# ToF_Sensor.net
KiCad netlist of a schematic drawn in Altium Designer
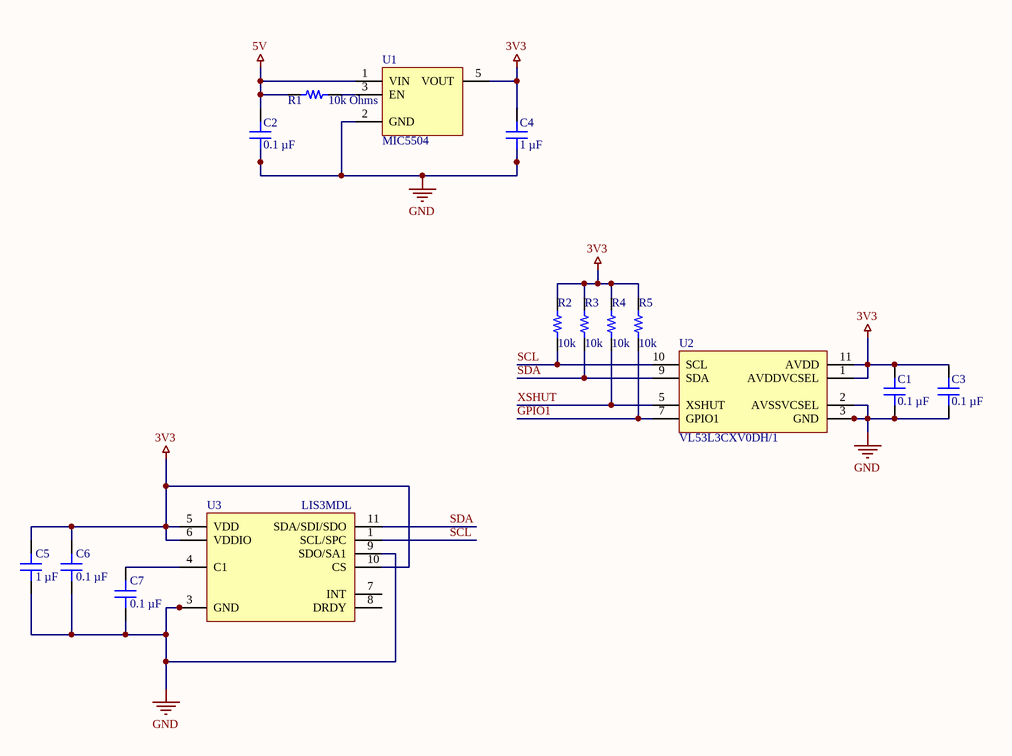
[diagram p0: ToF_Sensor.SchDoc]

(export (version "E")
  (design (tool "Eeschema 10.0.6"))
  (components
    (comp (ref "C1")
      (value "0.1 µF")
      (footprint "CAP 0402_1005")
      (description "CAP CER 0.1UF 16V X7R 0402")
      (fields (field (name "PART NUMBER") "C0402C104K4RACAUTO") (field (name "MANUFACTURER") "KEMET"))
      (libsource (lib "Celestial Altium Library - altium_library") (part "Capacitor"))
    )
    (comp (ref "C2")
      (value "0.1 µF")
      (footprint "CAP 0402_1005")
      (description "CAP CER 0.1UF 16V X7R 0402")
      (fields (field (name "PART NUMBER") "C0402C104K4RACAUTO") (field (name "MANUFACTURER") "KEMET"))
      (libsource (lib "Celestial Altium Library - altium_library") (part "Capacitor"))
    )
    (comp (ref "C3")
      (value "0.1 µF")
      (footprint "CAP 0402_1005")
      (description "CAP CER 0.1UF 16V X7R 0402")
      (fields (field (name "PART NUMBER") "C0402C104K4RACAUTO") (field (name "MANUFACTURER") "KEMET"))
      (libsource (lib "Celestial Altium Library - altium_library") (part "Capacitor"))
    )
    (comp (ref "C4")
      (value "1 µF")
      (footprint "CAP 0402_1005")
      (description "CAP CER 0.1UF 16V X7R 0402")
      (fields (field (name "PART NUMBER") "C0402C104K4RACAUTO") (field (name "MANUFACTURER") "KEMET"))
      (libsource (lib "Celestial Altium Library - altium_library") (part "Capacitor"))
    )
    (comp (ref "C5")
      (value "1 µF")
      (footprint "CAP 0402_1005")
      (description "CAP CER 0.1UF 16V X7R 0402")
      (fields (field (name "PART NUMBER") "C0402C104K4RACAUTO") (field (name "MANUFACTURER") "KEMET"))
      (libsource (lib "Celestial Altium Library - altium_library") (part "Capacitor"))
    )
    (comp (ref "C6")
      (value "0.1 µF")
      (footprint "CAP 0402_1005")
      (description "CAP CER 0.1UF 16V X7R 0402")
      (fields (field (name "PART NUMBER") "C0402C104K4RACAUTO") (field (name "MANUFACTURER") "KEMET"))
      (libsource (lib "Celestial Altium Library - altium_library") (part "Capacitor"))
    )
    (comp (ref "C7")
      (value "0.1 µF")
      (footprint "CAP 0402_1005")
      (description "CAP CER 0.1UF 16V X7R 0402")
      (fields (field (name "PART NUMBER") "C0402C104K4RACAUTO") (field (name "MANUFACTURER") "KEMET"))
      (libsource (lib "Celestial Altium Library - altium_library") (part "Capacitor"))
    )
    (comp (ref "R1")
      (value "10k Ohms")
      (footprint "RES 0402_1005")
      (description "RES 330 OHM 5% 1/16W 0402")
      (fields (field (name "PART NUMBER") "CRCW0402330RJNEDC") (field (name "MANUFACTURER") "Vishay Dale"))
      (libsource (lib "Celestial Altium Library - altium_library") (part "Resistor"))
    )
    (comp (ref "R2")
      (value "10k")
      (footprint "RES 0402_1005")
      (description "RES 330 OHM 5% 1/16W 0402")
      (fields (field (name "PART NUMBER") "CRCW0402330RJNEDC") (field (name "MANUFACTURER") "Vishay Dale"))
      (libsource (lib "Celestial Altium Library - altium_library") (part "Resistor"))
    )
    (comp (ref "R3")
      (value "10k")
      (footprint "RES 0402_1005")
      (description "RES 330 OHM 5% 1/16W 0402")
      (fields (field (name "PART NUMBER") "CRCW0402330RJNEDC") (field (name "MANUFACTURER") "Vishay Dale"))
      (libsource (lib "Celestial Altium Library - altium_library") (part "Resistor"))
    )
    (comp (ref "R4")
      (value "10k")
      (footprint "RES 0402_1005")
      (description "RES 330 OHM 5% 1/16W 0402")
      (fields (field (name "PART NUMBER") "CRCW0402330RJNEDC") (field (name "MANUFACTURER") "Vishay Dale"))
      (libsource (lib "Celestial Altium Library - altium_library") (part "Resistor"))
    )
    (comp (ref "R5")
      (value "10k")
      (footprint "RES 0402_1005")
      (description "RES 330 OHM 5% 1/16W 0402")
      (fields (field (name "PART NUMBER") "CRCW0402330RJNEDC") (field (name "MANUFACTURER") "Vishay Dale"))
      (libsource (lib "Celestial Altium Library - altium_library") (part "Resistor"))
    )
    (comp (ref "U1")
      (value "MIC5504")
      (footprint "TI SOT-23-5 DBV")
      (description "3.3V LDO")
      (libsource (lib "IC") (part "MIC5504-3.3YM5"))
    )
    (comp (ref "U2")
      (value "VL53L3CXV0DH/1")
      (footprint "XDCR_VL53L3CXV0DH/1")
      (description "Optical Sensor 118.110 (3m) I2C Output")
      (fields (field (name "MF") "STMicroelectronics"))
      (libsource (lib "IC") (part "VL53L3CXV0DH/1"))
    )
    (comp (ref "U3")
      (value "LIS3MDL")
      (footprint "LGA12_ST")
      (description "Magnetometer")
      (libsource (lib "IC") (part "LIS3MDL"))
    )
  )
  (nets
    (net (code "1") (name "/GPIO1") (class "Default")
      (node (ref "R5") (pin "2") (pinfunction "2_2") (pintype "passive"))
      (node (ref "U2") (pin "7") (pinfunction "GPIO1_7") (pintype "passive"))
    )
    (net (code "2") (name "/SCL") (class "Default")
      (node (ref "R2") (pin "2") (pinfunction "2_2") (pintype "passive"))
      (node (ref "U2") (pin "10") (pinfunction "SCL_10") (pintype "passive"))
      (node (ref "U3") (pin "1") (pinfunction "SCL/SPC_1") (pintype "passive"))
    )
    (net (code "3") (name "/SDA") (class "Default")
      (node (ref "R3") (pin "2") (pinfunction "2_2") (pintype "passive"))
      (node (ref "U2") (pin "9") (pinfunction "SDA_9") (pintype "passive"))
      (node (ref "U3") (pin "11") (pinfunction "SDA/SDI/SDO_11") (pintype "passive"))
    )
    (net (code "4") (name "/XSHUT") (class "Default")
      (node (ref "R4") (pin "2") (pinfunction "2_2") (pintype "passive"))
      (node (ref "U2") (pin "5") (pinfunction "XSHUT_5") (pintype "passive"))
    )
    (net (code "5") (name "3V3") (class "Default")
      (node (ref "C1") (pin "2") (pinfunction "2_2") (pintype "passive"))
      (node (ref "C3") (pin "2") (pinfunction "2_2") (pintype "passive"))
      (node (ref "C4") (pin "2") (pinfunction "2_2") (pintype "passive"))
      (node (ref "C5") (pin "1") (pinfunction "1_1") (pintype "passive"))
      (node (ref "C6") (pin "1") (pinfunction "1_1") (pintype "passive"))
      (node (ref "R2") (pin "1") (pinfunction "1_1") (pintype "passive"))
      (node (ref "R3") (pin "1") (pinfunction "1_1") (pintype "passive"))
      (node (ref "R4") (pin "1") (pinfunction "1_1") (pintype "passive"))
      (node (ref "R5") (pin "1") (pinfunction "1_1") (pintype "passive"))
      (node (ref "U1") (pin "5") (pinfunction "VOUT_5") (pintype "passive"))
      (node (ref "U2") (pin "1") (pinfunction "AVDDVCSEL_1") (pintype "passive"))
      (node (ref "U2") (pin "11") (pinfunction "AVDD_11") (pintype "passive"))
      (node (ref "U3") (pin "10") (pinfunction "CS_10") (pintype "passive"))
      (node (ref "U3") (pin "5") (pinfunction "VDD_5") (pintype "passive"))
      (node (ref "U3") (pin "6") (pinfunction "VDDIO_6") (pintype "passive"))
    )
    (net (code "6") (name "5V") (class "Default")
      (node (ref "C2") (pin "2") (pinfunction "2_2") (pintype "passive"))
      (node (ref "R1") (pin "2") (pinfunction "2_2") (pintype "passive"))
      (node (ref "U1") (pin "1") (pinfunction "VIN_1") (pintype "passive"))
    )
    (net (code "7") (name "GND") (class "Default")
      (node (ref "C1") (pin "1") (pinfunction "1_1") (pintype "passive"))
      (node (ref "C2") (pin "1") (pinfunction "1_1") (pintype "passive"))
      (node (ref "C3") (pin "1") (pinfunction "1_1") (pintype "passive"))
      (node (ref "C4") (pin "1") (pinfunction "1_1") (pintype "passive"))
      (node (ref "C5") (pin "2") (pinfunction "2_2") (pintype "passive"))
      (node (ref "C6") (pin "2") (pinfunction "2_2") (pintype "passive"))
      (node (ref "C7") (pin "2") (pinfunction "2_2") (pintype "passive"))
      (node (ref "U1") (pin "2") (pinfunction "GND_2") (pintype "passive"))
      (node (ref "U2") (pin "12") (pinfunction "GND_12") (pintype "passive"))
      (node (ref "U2") (pin "2") (pinfunction "AVSSVCSEL_2") (pintype "passive"))
      (node (ref "U2") (pin "3") (pinfunction "GND_3") (pintype "power_in"))
      (node (ref "U2") (pin "4") (pinfunction "GND_4") (pintype "power_in"))
      (node (ref "U2") (pin "6") (pinfunction "GND_6") (pintype "power_in"))
      (node (ref "U3") (pin "12") (pinfunction "Reserved_12") (pintype "passive"))
      (node (ref "U3") (pin "2") (pinfunction "Reserved_2") (pintype "passive"))
      (node (ref "U3") (pin "3") (pinfunction "GND_3") (pintype "passive"))
      (node (ref "U3") (pin "9") (pinfunction "SDO/SA1_9") (pintype "passive"))
    )
    (net (code "8") (name "Net-(U1-EN)") (class "Default")
      (node (ref "R1") (pin "1") (pinfunction "1_1") (pintype "passive"))
      (node (ref "U1") (pin "3") (pinfunction "EN_3") (pintype "passive"))
    )
    (net (code "9") (name "Net-(U3-C1)") (class "Default")
      (node (ref "C7") (pin "1") (pinfunction "1_1") (pintype "passive"))
      (node (ref "U3") (pin "4") (pinfunction "C1_4") (pintype "passive"))
    )
    (net (code "10") (name "unconnected-(U3-DRDY-Pad8)") (class "Default")
      (node (ref "U3") (pin "8") (pinfunction "DRDY_8") (pintype "passive"))
    )
    (net (code "11") (name "unconnected-(U3-INT-Pad7)") (class "Default")
      (node (ref "U3") (pin "7") (pinfunction "INT_7") (pintype "passive"))
    )
  )
)
